# Power.net
KiCad netlist of a schematic drawn in Altium Designer
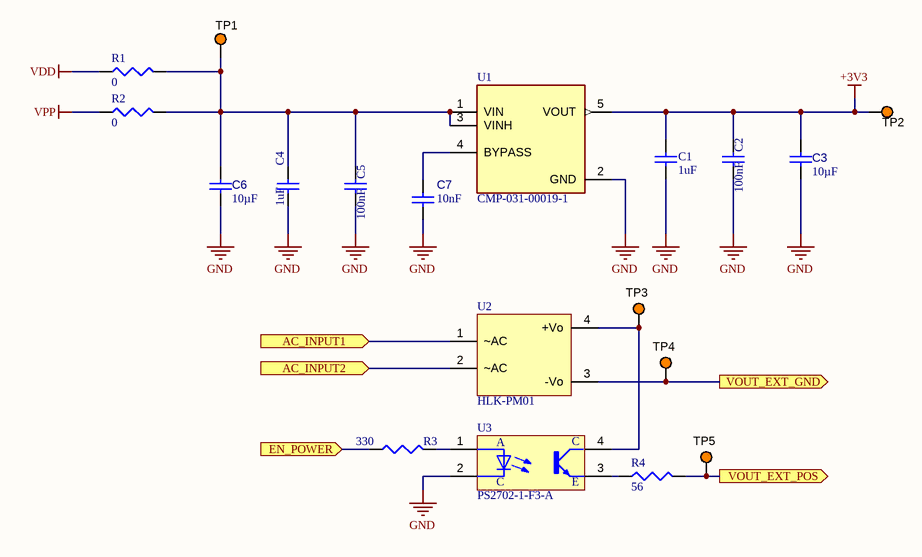
[diagram p0: Power.SchDoc]

(export (version "E")
  (design (tool "Eeschema 10.0.6"))
  (components
    (comp (ref "C1")
      (value "1uF")
      (footprint "EVIDC:C0603")
      (description "Cap_1uF_10%_X5R_25V_0603")
      (fields (field (name "MANUFACTURER") "Samsung") (field (name "MFR PART NO") "CL10A105KA8NNNC"))
      (libsource (lib "EVIDC") (part "Cap_1uF_25V_0603"))
    )
    (comp (ref "C2")
      (value "100nF")
      (footprint "C0603")
      (description "YAGEO - CC0603KRX7R8BB104 - CERAMIC CAPACITOR, 0.1UF, 25V, X7R, 10%, 0603, FULL REEL")
      (fields
        (field (name "TOLERANCE") "10%")
        (field (name "VOLTAGE") "25V")
        (field (name "SOURCE") "PTZLib.SchLib")
      )
      (libsource (lib "Kish Spark") (part "CAP-NP-2"))
    )
    (comp (ref "C3")
      (value "10µF")
      (footprint "0805")
      (description "Ceramic Capacitor, 10UF, 6.3V, X5R, 10%, 0805, Full Reel")
      (fields
        (field (name "MANUFACTURER") "KEMET")
        (field (name "MANUFACTURER PART NUMBER") "C0805C106K9PACTU")
      )
      (libsource (lib "Kish Spark") (part "CAP-NP-2"))
    )
    (comp (ref "C4")
      (value "1uF")
      (footprint "EVIDC:C0603")
      (description "Cap_1uF_10%_X5R_25V_0603")
      (fields (field (name "MANUFACTURER") "Samsung") (field (name "MFR PART NO") "CL10A105KA8NNNC"))
      (libsource (lib "EVIDC") (part "Cap_1uF_25V_0603"))
    )
    (comp (ref "C5")
      (value "100nF")
      (footprint "C0603")
      (description "YAGEO - CC0603KRX7R8BB104 - CERAMIC CAPACITOR, 0.1UF, 25V, X7R, 10%, 0603, FULL REEL")
      (fields
        (field (name "TOLERANCE") "10%")
        (field (name "VOLTAGE") "25V")
        (field (name "SOURCE") "PTZLib.SchLib")
      )
      (libsource (lib "Kish Spark") (part "CAP-NP-2"))
    )
    (comp (ref "C6")
      (value "10µF")
      (footprint "0805")
      (description "Ceramic Capacitor, 10UF, 6.3V, X5R, 10%, 0805, Full Reel")
      (fields
        (field (name "MANUFACTURER") "KEMET")
        (field (name "MANUFACTURER PART NUMBER") "C0805C106K9PACTU")
      )
      (libsource (lib "Kish Spark") (part "CAP-NP-2"))
    )
    (comp (ref "C7")
      (value "10nF")
      (footprint "C0603")
      (description "0603 10nF 50 V ±10 % Tolerance X7R Surface Mount Multilayer Ceramic Capacitor")
      (fields (field (name "TOLERANCE") "10%") (field (name "MANUFACTURER") "Kyocera AVX"))
      (libsource (lib "Kish Spark") (part "CAP-NP-2"))
    )
    (comp (ref "R1")
      (value "0")
      (footprint "R0603")
      (description "Res Thkflm 0603 0 Ohm Jumper 1/10W 100Ppm/ C Smd Rohs Compliant: Yes")
      (fields (field (name "Comment") "RMCF0603ZT0R00") (field (name "SOURCE") "PTZLib.SchLib"))
      (libsource (lib "Kish Spark") (part "CRCW060349R9FKEAC"))
    )
    (comp (ref "R2")
      (value "0")
      (footprint "R0603")
      (description "Res Thkflm 0603 0 Ohm Jumper 1/10W 100Ppm/ C Smd Rohs Compliant: Yes")
      (fields (field (name "Comment") "RMCF0603ZT0R00") (field (name "SOURCE") "PTZLib.SchLib"))
      (libsource (lib "Kish Spark") (part "CRCW060349R9FKEAC"))
    )
    (comp (ref "R3")
      (value "330")
      (footprint "R0603")
      (description "Res Thick Film 0603 330 Ohm 1% 0.1W(1/10W) ±100ppm/C Pad SMD T/R")
      (fields (field (name "TOLERANCE") "1%") (field (name "MANUFACTURER") "Yageo"))
      (libsource (lib "Kish Spark") (part "CRCW06030000Z0EAHP"))
    )
    (comp (ref "R4")
      (value "56")
      (footprint "R2512")
      (description "Res Thick Film 2512 56 Ohm 5% 2W ±100ppm/°C Molded SMD SMD T/R")
      (fields
        (field (name "MANUFACTURER") "TE Connectivity")
        (field (name "MANUFACTURER PART NUMBER") "4-1879501-3")
      )
      (libsource (lib "Kish Spark") (part "RC0805FR-1018KL (2)"))
    )
    (comp (ref "TP1")
      (value "5003")
      (footprint "KSTN-5003")
      (description "Test Point, Orange, Height 4.6 mm, Tail Length 3 mm, 1-Pin THD, RoHS")
      (fields (field (name "MANUFACTURER") "Keystone"))
      (libsource (lib "Kish Spark") (part "TESTPOINT_ORANGE"))
    )
    (comp (ref "TP2")
      (value "5003")
      (footprint "KSTN-5003")
      (description "Test Point, Orange, Height 4.6 mm, Tail Length 3 mm, 1-Pin THD, RoHS")
      (fields (field (name "MANUFACTURER") "Keystone"))
      (libsource (lib "Kish Spark") (part "TESTPOINT_ORANGE"))
    )
    (comp (ref "TP3")
      (value "5003")
      (footprint "KSTN-5003")
      (description "Test Point, Orange, Height 4.6 mm, Tail Length 3 mm, 1-Pin THD, RoHS")
      (fields (field (name "MANUFACTURER") "Keystone"))
      (libsource (lib "Kish Spark") (part "TESTPOINT_ORANGE"))
    )
    (comp (ref "TP4")
      (value "5003")
      (footprint "KSTN-5003")
      (description "Test Point, Orange, Height 4.6 mm, Tail Length 3 mm, 1-Pin THD, RoHS")
      (fields (field (name "MANUFACTURER") "Keystone"))
      (libsource (lib "Kish Spark") (part "TESTPOINT_ORANGE"))
    )
    (comp (ref "TP5")
      (value "5003")
      (footprint "KSTN-5003")
      (description "Test Point, Orange, Height 4.6 mm, Tail Length 3 mm, 1-Pin THD, RoHS")
      (fields (field (name "MANUFACTURER") "Keystone"))
      (libsource (lib "Kish Spark") (part "TESTPOINT_ORANGE"))
    )
    (comp (ref "U1")
      (value "CMP-031-00019-1")
      (footprint "LM")
      (description "Linear Voltage Regulator IC Positive Fixed 1 Output 3.3V 150mA SOT-23-5")
      (fields
        (field (name "MANUFACTURER") "STMicroelectronics")
        (field (name "MANUFACTURER PART NUMBER") "LD3985M33R")
      )
      (libsource (lib "Kish Spark") (part "LD3985M33R"))
    )
    (comp (ref "U2")
      (value "HLK-PM01")
      (footprint "HLK-PMO1")
      (description "AC-DC Module HLK-PM01 5V 3W Hi-Link")
      (libsource (lib "Kish Spark") (part "HLK_2M05"))
    )
    (comp (ref "U3")
      (value "PS2702-1-F3-A")
      (footprint "SOP4")
      (description "High Isolation Voltage Darlington Transistor SOP MULTI Photocoupler Series")
      (fields (field (name "MANUFACTURER") "Renesas"))
      (libsource (lib "Kish Spark") (part "PS2702-1-F3-A"))
    )
  )
  (nets
    (net (code "1") (name "+3V3") (class "Default")
      (node (ref "C1") (pin "2") (pinfunction "2_2") (pintype "passive"))
      (node (ref "C2") (pin "1") (pinfunction "1_1") (pintype "passive"))
      (node (ref "C3") (pin "2") (pinfunction "2_2") (pintype "passive"))
      (node (ref "TP2") (pin "1") (pinfunction "1_1") (pintype "passive"))
      (node (ref "U1") (pin "5") (pinfunction "VOUT_5") (pintype "output"))
    )
    (net (code "2") (name "/AC_INPUT1") (class "Default")
      (node (ref "U2") (pin "1") (pinfunction "~AC_1") (pintype "passive"))
    )
    (net (code "3") (name "/AC_INPUT2") (class "Default")
      (node (ref "U2") (pin "2") (pinfunction "~AC_2") (pintype "passive"))
    )
    (net (code "4") (name "/EN_POWER") (class "Default")
      (node (ref "R3") (pin "2") (pinfunction "2_2") (pintype "passive"))
    )
    (net (code "5") (name "/VOUT_EXT_GND") (class "Default")
      (node (ref "TP4") (pin "1") (pinfunction "1_1") (pintype "passive"))
      (node (ref "U2") (pin "3") (pinfunction "-Vo_3") (pintype "passive"))
    )
    (net (code "6") (name "/VOUT_EXT_POS") (class "Default")
      (node (ref "R4") (pin "2") (pinfunction "2_2") (pintype "passive"))
      (node (ref "TP5") (pin "1") (pinfunction "1_1") (pintype "passive"))
    )
    (net (code "7") (name "GND") (class "Default")
      (node (ref "C1") (pin "1") (pinfunction "1_1") (pintype "passive"))
      (node (ref "C2") (pin "2") (pinfunction "2_2") (pintype "passive"))
      (node (ref "C3") (pin "1") (pinfunction "1_1") (pintype "passive"))
      (node (ref "C4") (pin "1") (pinfunction "1_1") (pintype "passive"))
      (node (ref "C5") (pin "2") (pinfunction "2_2") (pintype "passive"))
      (node (ref "C6") (pin "1") (pinfunction "1_1") (pintype "passive"))
      (node (ref "C7") (pin "1") (pinfunction "1_1") (pintype "passive"))
      (node (ref "U1") (pin "2") (pinfunction "GND_2") (pintype "power_in"))
      (node (ref "U3") (pin "2") (pinfunction "C_2") (pintype "passive"))
    )
    (net (code "8") (name "Net-(U1-BYPASS)") (class "Default")
      (node (ref "C7") (pin "2") (pinfunction "2_2") (pintype "passive"))
      (node (ref "U1") (pin "4") (pinfunction "BYPASS_4") (pintype "passive"))
    )
    (net (code "9") (name "Net-(U1-VIN)") (class "Default")
      (node (ref "C4") (pin "2") (pinfunction "2_2") (pintype "passive"))
      (node (ref "C5") (pin "1") (pinfunction "1_1") (pintype "passive"))
      (node (ref "C6") (pin "2") (pinfunction "2_2") (pintype "passive"))
      (node (ref "R1") (pin "2") (pinfunction "2_2") (pintype "passive"))
      (node (ref "R2") (pin "2") (pinfunction "2_2") (pintype "passive"))
      (node (ref "TP1") (pin "1") (pinfunction "1_1") (pintype "passive"))
      (node (ref "U1") (pin "1") (pinfunction "VIN_1") (pintype "passive"))
      (node (ref "U1") (pin "3") (pinfunction "VINH_3") (pintype "passive"))
    )
    (net (code "10") (name "Net-(U2-+Vo)") (class "Default")
      (node (ref "TP3") (pin "1") (pinfunction "1_1") (pintype "passive"))
      (node (ref "U2") (pin "4") (pinfunction "+Vo_4") (pintype "passive"))
      (node (ref "U3") (pin "4") (pinfunction "CO_4") (pintype "passive"))
    )
    (net (code "11") (name "Net-(U3-A)") (class "Default")
      (node (ref "R3") (pin "1") (pinfunction "1_1") (pintype "passive"))
      (node (ref "U3") (pin "1") (pinfunction "A_1") (pintype "passive"))
    )
    (net (code "12") (name "Net-(U3-E)") (class "Default")
      (node (ref "R4") (pin "1") (pinfunction "1_1") (pintype "passive"))
      (node (ref "U3") (pin "3") (pinfunction "E_3") (pintype "passive"))
    )
    (net (code "13") (name "VDD") (class "Default")
      (node (ref "R1") (pin "1") (pinfunction "1_1") (pintype "passive"))
    )
    (net (code "14") (name "VPP") (class "Default")
      (node (ref "R2") (pin "1") (pinfunction "1_1") (pintype "passive"))
    )
  )
)
